# POWER_GATEWAY.net
KiCad netlist of a schematic drawn in Altium Designer
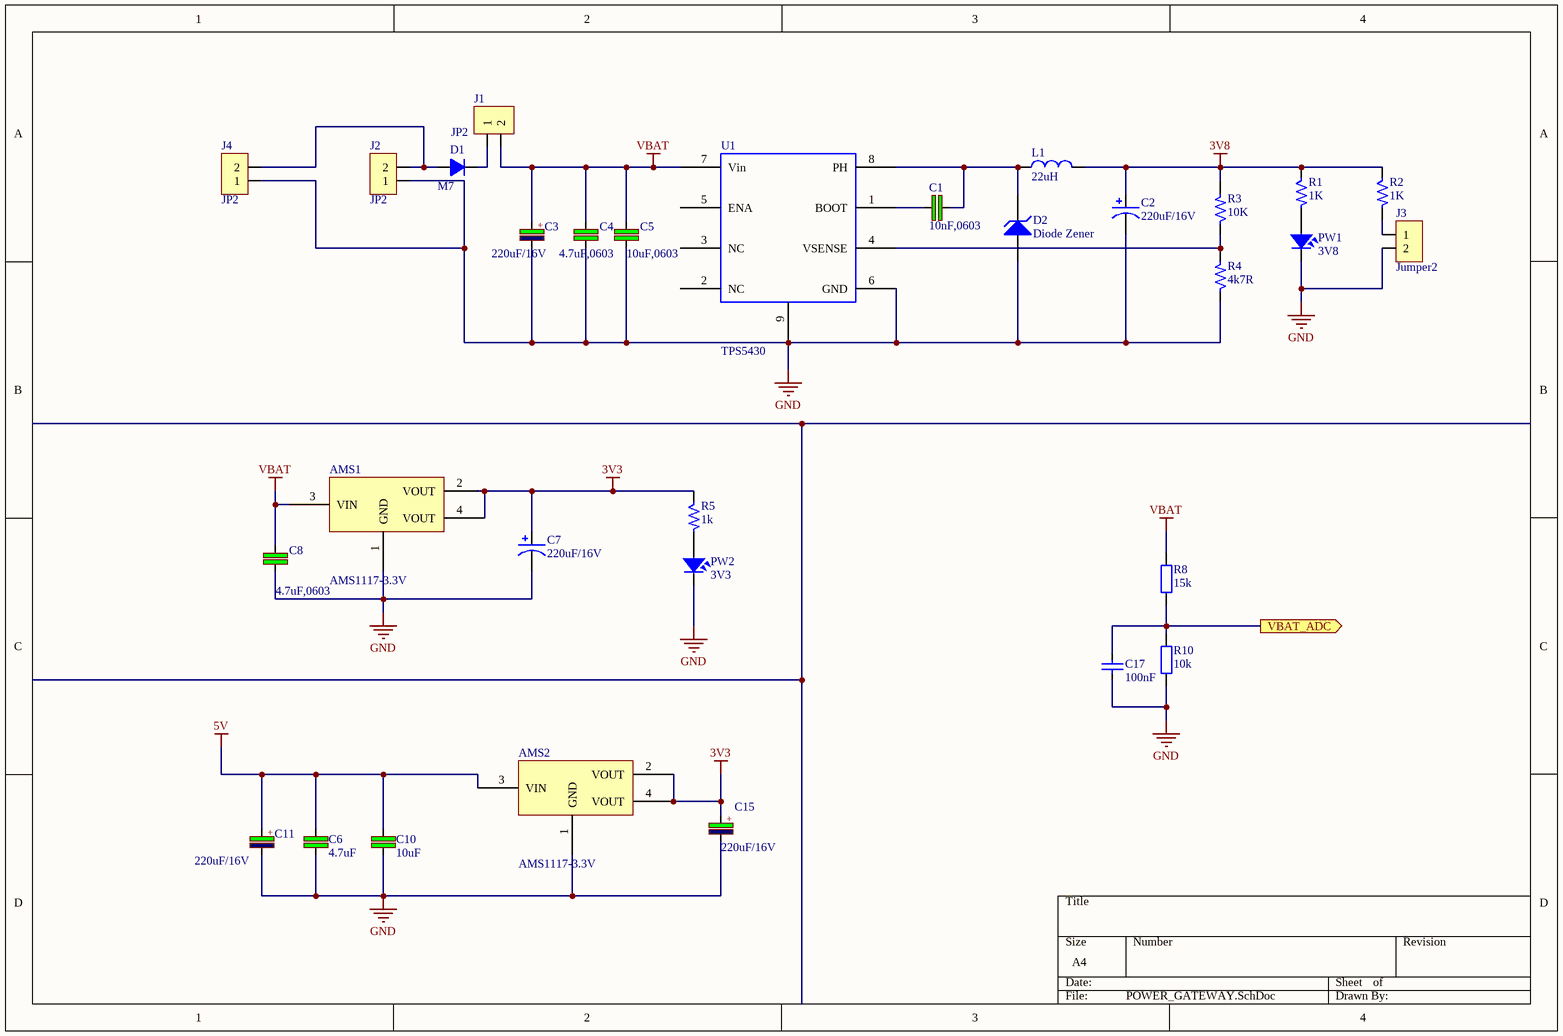
[diagram p0: POWER_GATEWAY.SchDoc]

(export (version "E")
  (design (tool "Eeschema 10.0.6"))
  (components
    (comp (ref "AMS1")
      (value "AMS1117-3.3V")
      (footprint "SOT223")
      (description "Dán")
      (libsource (lib "IC") (part "AMS1117 SMD"))
    )
    (comp (ref "AMS2")
      (value "AMS1117-3.3V")
      (footprint "SOT223")
      (description "Dán")
      (libsource (lib "IC") (part "AMS1117 SMD"))
    )
    (comp (ref "C1")
      (value "10nF,0603")
      (footprint "CAP_0603")
      (description "4.7µF ±10% 35V Ceramic Capacitor X5R 0805 (2012 Metric)")
      (fields
        (field (name "MANUFACTURER") "Samsung Electro-Mechanics")
        (field (name "PART NUMBER") "CL21A475KLCLQNC")
      )
      (libsource (lib "Anh_Trung") (part "C"))
    )
    (comp (ref "C2")
      (value "220uF/16V")
      (footprint "C5mm")
      (description "Polarized Capacitor (Axial)")
      (fields (field (name "PUBLISHER") "Altium Limited"))
      (libsource (lib "My Library") (part "Cap Pol"))
    )
    (comp (ref "C3")
      (value "220uF/16V")
      (footprint "C8mm")
      (description "Cap 470uF/63V")
      (libsource (lib "Main") (part "CP3"))
    )
    (comp (ref "C4")
      (value "4.7uF,0603")
      (footprint "CAP_0603")
      (description "4.7µF ±10% 35V Ceramic Capacitor X5R 0805 (2012 Metric)")
      (fields
        (field (name "MANUFACTURER") "Samsung Electro-Mechanics")
        (field (name "PART NUMBER") "CL21A475KLCLQNC")
      )
      (libsource (lib "") (part "C_1"))
    )
    (comp (ref "C5")
      (value "10uF,0603")
      (footprint "CAP_0603")
      (description "4.7µF ±10% 35V Ceramic Capacitor X5R 0805 (2012 Metric)")
      (fields
        (field (name "MANUFACTURER") "Samsung Electro-Mechanics")
        (field (name "PART NUMBER") "CL21A475KLCLQNC")
      )
      (libsource (lib "") (part "C_1"))
    )
    (comp (ref "C6")
      (value "4.7uF")
      (footprint "CAP_0603")
      (description "Cap SMD")
      (fields
        (field (name "MANUFACTURER") "Samsung Electro-Mechanics")
        (field (name "PART NUMBER") "CL21A106KPFNNNG")
      )
      (libsource (lib "Anh_Trung") (part "C"))
    )
    (comp (ref "C7")
      (value "220uF/16V")
      (footprint "C5mm")
      (description "Polarized Capacitor (Axial)")
      (fields (field (name "PUBLISHER") "Altium Limited"))
      (libsource (lib "My Library") (part "Cap Pol"))
    )
    (comp (ref "C8")
      (value "4.7uF,0603")
      (footprint "CAP_0603")
      (description "4.7µF ±10% 35V Ceramic Capacitor X5R 0805 (2012 Metric)")
      (fields
        (field (name "MANUFACTURER") "Samsung Electro-Mechanics")
        (field (name "PART NUMBER") "CL21A475KLCLQNC")
      )
      (libsource (lib "") (part "C_1"))
    )
    (comp (ref "C10")
      (value "10uF")
      (footprint "CAP_0603")
      (description "Cap SMD")
      (fields
        (field (name "MANUFACTURER") "Samsung Electro-Mechanics")
        (field (name "PART NUMBER") "CL21A106KPFNNNG")
      )
      (libsource (lib "Anh_Trung") (part "C"))
    )
    (comp (ref "C11")
      (value "220uF/16V")
      (footprint "C8mm")
      (description "Cap 470uF/63V")
      (libsource (lib "Main") (part "CP3"))
    )
    (comp (ref "C15")
      (value "220uF/16V")
      (footprint "C5mm")
      (description "Cap 470uF/63V")
      (libsource (lib "Main") (part "CP3"))
    )
    (comp (ref "C17")
      (value "100nF")
      (footprint "CAP_0603")
      (description "Capacitor")
      (fields (field (name "PUBLISHER") "Altium Limited"))
      (libsource (lib "My Library") (part "CapSMD"))
    )
    (comp (ref "D1")
      (value "M7")
      (footprint "SMA")
      (description "Diode 1A")
      (libsource (lib "Main") (part "D1A"))
    )
    (comp (ref "D2")
      (value "Diode Zener")
      (footprint "SMA")
      (description "Zener Diode")
      (fields (field (name "PUBLISHER") "Altium Limited"))
      (libsource (lib "My Library 2") (part "Diode Zener"))
    )
    (comp (ref "J1")
      (value "JP2")
      (footprint "KF2-5.08")
      (description "WR-PHD 2.54 mm Angled Socket Header")
      (fields
        (field (name "MANUFACTURER") "Würth Elektronik eiSos GmbH")
        (field (name "PARTNO") "613002143121")
        (field (name "CREATED BY") "Karrer Zheng")
      )
      (libsource (lib "") (part "JP2_1"))
    )
    (comp (ref "J2")
      (value "JP2")
      (footprint "KF2-5.08")
      (description "WR-PHD 2.54 mm Angled Socket Header")
      (fields
        (field (name "MANUFACTURER") "Würth Elektronik eiSos GmbH")
        (field (name "PARTNO") "613002143121")
        (field (name "CREATED BY") "Karrer Zheng")
      )
      (libsource (lib "My Library") (part "JP2"))
    )
    (comp (ref "J3")
      (value "Jumper2")
      (footprint "CON2")
      (description "WR-PHD 2.54 mm Angled Socket Header")
      (fields
        (field (name "MANUFACTURER") "Würth Elektronik eiSos GmbH")
        (field (name "PARTNO") "613002143121")
        (field (name "CREATED BY") "Karrer Zheng")
      )
      (libsource (lib "") (part "JP2_2"))
    )
    (comp (ref "J4")
      (value "JP2")
      (footprint "KF2-5.08")
      (description "WR-PHD 2.54 mm Angled Socket Header")
      (fields
        (field (name "MANUFACTURER") "Würth Elektronik eiSos GmbH")
        (field (name "PARTNO") "613002143121")
        (field (name "CREATED BY") "Karrer Zheng")
      )
      (libsource (lib "My Library") (part "JP2"))
    )
    (comp (ref "L1")
      (value "22uH")
      (footprint "Inductor_SMD")
      (description "22µH Shielded Inductor 1.65A 96mOhm Max Nonstandard")
      (fields (field (name "MANUFACTURER") "Bourns Inc.") (field (name "PART NUMBER") "SRR0745A-220M"))
      (libsource (lib "Main") (part "L1"))
    )
    (comp (ref "PW1")
      (value "3V8")
      (footprint "LED-0805-Blue")
      (description "LED RED DIFFUSED 0805 SMD")
      (fields
        (field (name "MANUFACTURER") "OSRAM Opto Semiconductors Inc.")
        (field (name "PART NUMBER") "LS R976-NR-1")
      )
      (libsource (lib "Anh_Trung") (part "LED"))
    )
    (comp (ref "PW2")
      (value "3V3")
      (footprint "LED-0805-Blue")
      (description "LED RED DIFFUSED 0805 SMD")
      (fields
        (field (name "MANUFACTURER") "OSRAM Opto Semiconductors Inc.")
        (field (name "PART NUMBER") "LS R976-NR-1")
      )
      (libsource (lib "Anh_Trung") (part "LED"))
    )
    (comp (ref "R1")
      (value "1K")
      (footprint "RES-SMD-0805")
      (description "Resistor 1/4W")
      (fields (field (name "MANUFACTURER") "Yageo") (field (name "PART NUMBER") "RC0805FR-071KL"))
      (libsource (lib "Anh_Trung") (part "R"))
    )
    (comp (ref "R2")
      (value "1K")
      (footprint "RES-SMD-0805")
      (description "Resistor 1/4W")
      (fields (field (name "MANUFACTURER") "Yageo") (field (name "PART NUMBER") "RC0805FR-071KL"))
      (libsource (lib "Anh_Trung") (part "R"))
    )
    (comp (ref "R3")
      (value "10K")
      (footprint "RES-SMD-0603")
      (description "RES SMD 10K OHM 1% 1/8W 0805")
      (fields (field (name "MANUFACTURER") "Yageo") (field (name "PART NUMBER") "RC0805FR-0710KL"))
      (libsource (lib "Anh_Trung") (part "R"))
    )
    (comp (ref "R4")
      (value "4k7R")
      (footprint "RES-SMD-0603")
      (description "RES SMD 3.3K OHM 1% 1/8W 0805")
      (fields (field (name "MANUFACTURER") "Yageo") (field (name "PART NUMBER") "RC0805FR-073K3L"))
      (libsource (lib "Anh_Trung") (part "R"))
    )
    (comp (ref "R5")
      (value "1k")
      (footprint "RES-SMD-0603")
      (description "Resistor 1/4W")
      (fields (field (name "MANUFACTURER") "Yageo") (field (name "PART NUMBER") "RC0805FR-071KL"))
      (libsource (lib "Anh_Trung") (part "R"))
    )
    (comp (ref "R8")
      (value "15k")
      (footprint "RES-SMD-0805")
      (description "Resistor SMD")
      (fields
        (field (name "MANUFACTURER") "Generic Components")
        (field (name "PUBLISHER") "Altium Hobart Technology Centre")
      )
      (libsource (lib "My Library") (part "Resistor - SMD"))
    )
    (comp (ref "R10")
      (value "10k")
      (footprint "RES-SMD-0805")
      (description "Resistor SMD")
      (fields
        (field (name "MANUFACTURER") "Generic Components")
        (field (name "PUBLISHER") "Altium Hobart Technology Centre")
      )
      (libsource (lib "My Library") (part "Resistor - SMD"))
    )
    (comp (ref "U1")
      (value "TPS5430")
      (footprint "TPS5430-2")
      (fields (field (name "NAME") "TPS5430"))
      (libsource (lib "My Library 2") (part "TPS5430"))
    )
  )
  (nets
    (net (code "1") (name "/VBAT_ADC") (class "Default")
      (node (ref "C17") (pin "2") (pinfunction "2_2") (pintype "passive"))
      (node (ref "R10") (pin "2") (pinfunction "2_2") (pintype "passive"))
      (node (ref "R8") (pin "1") (pinfunction "1_1") (pintype "passive"))
    )
    (net (code "2") (name "3V3") (class "Default")
      (node (ref "AMS1") (pin "2") (pinfunction "VOUT_2") (pintype "passive"))
      (node (ref "AMS1") (pin "4") (pinfunction "VOUT_4") (pintype "passive"))
      (node (ref "AMS2") (pin "2") (pinfunction "VOUT_2") (pintype "passive"))
      (node (ref "AMS2") (pin "4") (pinfunction "VOUT_4") (pintype "passive"))
      (node (ref "C15") (pin "1") (pinfunction "1_1") (pintype "passive"))
      (node (ref "C7") (pin "1") (pinfunction "1_1") (pintype "passive"))
      (node (ref "R5") (pin "1") (pinfunction "1_1") (pintype "passive"))
    )
    (net (code "3") (name "3V8") (class "Default")
      (node (ref "C2") (pin "1") (pinfunction "1_1") (pintype "passive"))
      (node (ref "L1") (pin "2") (pinfunction "2_2") (pintype "passive"))
      (node (ref "R1") (pin "1") (pinfunction "1_1") (pintype "passive"))
      (node (ref "R2") (pin "1") (pinfunction "1_1") (pintype "passive"))
      (node (ref "R3") (pin "2") (pinfunction "2_2") (pintype "passive"))
    )
    (net (code "4") (name "5V") (class "Default")
      (node (ref "AMS2") (pin "3") (pinfunction "VIN_3") (pintype "passive"))
      (node (ref "C10") (pin "1") (pinfunction "1_1") (pintype "passive"))
      (node (ref "C11") (pin "1") (pinfunction "1_1") (pintype "passive"))
      (node (ref "C6") (pin "1") (pinfunction "1_1") (pintype "passive"))
    )
    (net (code "5") (name "GND") (class "Default")
      (node (ref "AMS1") (pin "1") (pinfunction "GND_1") (pintype "passive"))
      (node (ref "AMS2") (pin "1") (pinfunction "GND_1") (pintype "passive"))
      (node (ref "C10") (pin "2") (pinfunction "2_2") (pintype "passive"))
      (node (ref "C11") (pin "2") (pinfunction "2_2") (pintype "passive"))
      (node (ref "C15") (pin "2") (pinfunction "2_2") (pintype "passive"))
      (node (ref "C17") (pin "1") (pinfunction "1_1") (pintype "passive"))
      (node (ref "C2") (pin "2") (pinfunction "2_2") (pintype "passive"))
      (node (ref "C3") (pin "2") (pinfunction "2_2") (pintype "passive"))
      (node (ref "C4") (pin "1") (pinfunction "1_1") (pintype "passive"))
      (node (ref "C5") (pin "1") (pinfunction "1_1") (pintype "passive"))
      (node (ref "C6") (pin "2") (pinfunction "2_2") (pintype "passive"))
      (node (ref "C7") (pin "2") (pinfunction "2_2") (pintype "passive"))
      (node (ref "C8") (pin "1") (pinfunction "1_1") (pintype "passive"))
      (node (ref "D2") (pin "1") (pinfunction "A_1") (pintype "passive"))
      (node (ref "J2") (pin "1") (pinfunction "1_1") (pintype "passive"))
      (node (ref "J3") (pin "2") (pinfunction "2_2") (pintype "passive"))
      (node (ref "J4") (pin "1") (pinfunction "1_1") (pintype "passive"))
      (node (ref "PW1") (pin "2") (pinfunction "2_2") (pintype "passive"))
      (node (ref "PW2") (pin "2") (pinfunction "2_2") (pintype "passive"))
      (node (ref "R10") (pin "1") (pinfunction "1_1") (pintype "passive"))
      (node (ref "R4") (pin "1") (pinfunction "1_1") (pintype "passive"))
      (node (ref "U1") (pin "6") (pinfunction "GND_6") (pintype "passive"))
      (node (ref "U1") (pin "9") (pinfunction "PWR_PAD_9") (pintype "passive"))
    )
    (net (code "6") (name "Net-(D1-A)") (class "Default")
      (node (ref "D1") (pin "1") (pinfunction "A_1") (pintype "passive"))
      (node (ref "J2") (pin "2") (pinfunction "2_2") (pintype "passive"))
      (node (ref "J4") (pin "2") (pinfunction "2_2") (pintype "passive"))
    )
    (net (code "7") (name "Net-(D1-K)") (class "Default")
      (node (ref "D1") (pin "2") (pinfunction "K_2") (pintype "passive"))
      (node (ref "J1") (pin "1") (pinfunction "1_1") (pintype "passive"))
    )
    (net (code "8") (name "Net-(D2-K)") (class "Default")
      (node (ref "C1") (pin "1") (pinfunction "1_1") (pintype "passive"))
      (node (ref "D2") (pin "2") (pinfunction "K_2") (pintype "passive"))
      (node (ref "L1") (pin "1") (pinfunction "1_1") (pintype "passive"))
      (node (ref "U1") (pin "8") (pinfunction "PH_8") (pintype "passive"))
    )
    (net (code "9") (name "Net-(J3-Pad1)") (class "Default")
      (node (ref "J3") (pin "1") (pinfunction "1_1") (pintype "passive"))
      (node (ref "R2") (pin "2") (pinfunction "2_2") (pintype "passive"))
    )
    (net (code "10") (name "Net-(PW1-Pad1)") (class "Default")
      (node (ref "PW1") (pin "1") (pinfunction "1_1") (pintype "passive"))
      (node (ref "R1") (pin "2") (pinfunction "2_2") (pintype "passive"))
    )
    (net (code "11") (name "Net-(PW2-Pad1)") (class "Default")
      (node (ref "PW2") (pin "1") (pinfunction "1_1") (pintype "passive"))
      (node (ref "R5") (pin "2") (pinfunction "2_2") (pintype "passive"))
    )
    (net (code "12") (name "Net-(U1-BOOT)") (class "Default")
      (node (ref "C1") (pin "2") (pinfunction "2_2") (pintype "passive"))
      (node (ref "U1") (pin "1") (pinfunction "BOOT_1") (pintype "passive"))
    )
    (net (code "13") (name "Net-(U1-VSENSE)") (class "Default")
      (node (ref "R3") (pin "1") (pinfunction "1_1") (pintype "passive"))
      (node (ref "R4") (pin "2") (pinfunction "2_2") (pintype "passive"))
      (node (ref "U1") (pin "4") (pinfunction "VSENSE_4") (pintype "passive"))
    )
    (net (code "14") (name "VBAT") (class "Default")
      (node (ref "AMS1") (pin "3") (pinfunction "VIN_3") (pintype "passive"))
      (node (ref "C3") (pin "1") (pinfunction "1_1") (pintype "passive"))
      (node (ref "C4") (pin "2") (pinfunction "2_2") (pintype "passive"))
      (node (ref "C5") (pin "2") (pinfunction "2_2") (pintype "passive"))
      (node (ref "C8") (pin "2") (pinfunction "2_2") (pintype "passive"))
      (node (ref "J1") (pin "2") (pinfunction "2_2") (pintype "passive"))
      (node (ref "R8") (pin "2") (pinfunction "2_2") (pintype "passive"))
      (node (ref "U1") (pin "7") (pinfunction "Vin_7") (pintype "passive"))
    )
    (net (code "15") (name "unconnected-(U1-ENA-Pad5)") (class "Default")
      (node (ref "U1") (pin "5") (pinfunction "ENA_5") (pintype "passive"))
    )
    (net (code "16") (name "unconnected-(U1-NC-Pad2)") (class "Default")
      (node (ref "U1") (pin "2") (pinfunction "NC_2") (pintype "passive"))
    )
    (net (code "17") (name "unconnected-(U1-NC-Pad3)") (class "Default")
      (node (ref "U1") (pin "3") (pinfunction "NC_3") (pintype "passive"))
    )
  )
)
